# ATMEGA16_S52.net
KiCad netlist of a schematic drawn in Altium Designer
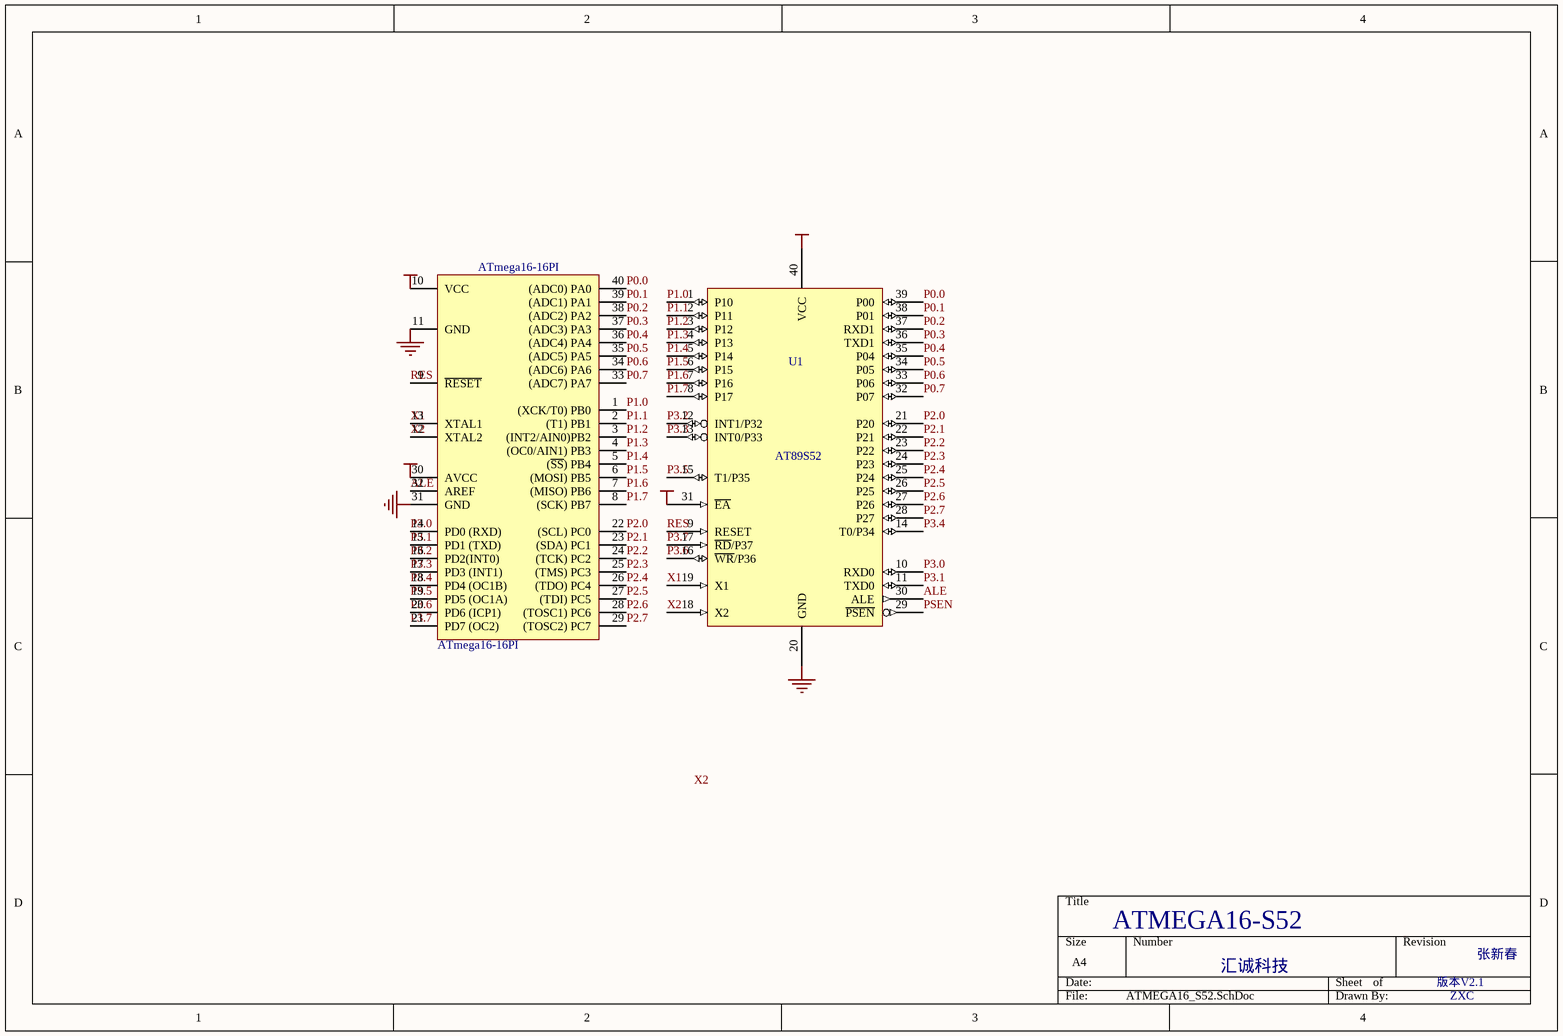
[diagram p0: ATMEGA16_S52.SchDoc]

(export (version "E")
  (design (tool "Eeschema 10.0.6"))
  (components
    (comp (ref "ATmega16-16PI")
      (value "ATmega16-16PI")
      (footprint "底座DIP-40/引脚15.24mm")
      (description "8 位微处理器/40引脚")
      (fields (field (name "发布者") "磊元工作室"))
      (libsource (lib "微控制处理器") (part "ATmega16-P"))
    )
    (comp (ref "U1") (value "AT89S52") (footprint "DIP-40") (libsource (lib "OldCow1 (2)") (part "8051")))
  )
  (nets
    (net (code "1") (name "/ALE") (class "Default")
      (node (ref "ATmega16-16PI") (pin "32") (pinfunction "AREF_32") (pintype "passive"))
      (node (ref "U1") (pin "30") (pinfunction "ALE_30") (pintype "output"))
    )
    (net (code "2") (name "/P0.0") (class "Default")
      (node (ref "ATmega16-16PI") (pin "40") (pinfunction "(ADC0)_PA0_40") (pintype "passive"))
      (node (ref "U1") (pin "39") (pinfunction "P00_39") (pintype "bidirectional"))
    )
    (net (code "3") (name "/P0.1") (class "Default")
      (node (ref "ATmega16-16PI") (pin "39") (pinfunction "(ADC1)_PA1_39") (pintype "passive"))
      (node (ref "U1") (pin "38") (pinfunction "P01_38") (pintype "bidirectional"))
    )
    (net (code "4") (name "/P0.2") (class "Default")
      (node (ref "ATmega16-16PI") (pin "38") (pinfunction "(ADC2)_PA2_38") (pintype "passive"))
      (node (ref "U1") (pin "37") (pinfunction "RXD1_37") (pintype "bidirectional"))
    )
    (net (code "5") (name "/P0.3") (class "Default")
      (node (ref "ATmega16-16PI") (pin "37") (pinfunction "(ADC3)_PA3_37") (pintype "passive"))
      (node (ref "U1") (pin "36") (pinfunction "TXD1_36") (pintype "bidirectional"))
    )
    (net (code "6") (name "/P0.4") (class "Default")
      (node (ref "ATmega16-16PI") (pin "36") (pinfunction "(ADC4)_PA4_36") (pintype "passive"))
      (node (ref "U1") (pin "35") (pinfunction "P04_35") (pintype "bidirectional"))
    )
    (net (code "7") (name "/P0.5") (class "Default")
      (node (ref "ATmega16-16PI") (pin "35") (pinfunction "(ADC5)_PA5_35") (pintype "passive"))
      (node (ref "U1") (pin "34") (pinfunction "P05_34") (pintype "bidirectional"))
    )
    (net (code "8") (name "/P0.6") (class "Default")
      (node (ref "ATmega16-16PI") (pin "34") (pinfunction "(ADC6)_PA6_34") (pintype "passive"))
      (node (ref "U1") (pin "33") (pinfunction "P06_33") (pintype "bidirectional"))
    )
    (net (code "9") (name "/P0.7") (class "Default")
      (node (ref "ATmega16-16PI") (pin "33") (pinfunction "(ADC7)_PA7_33") (pintype "passive"))
      (node (ref "U1") (pin "32") (pinfunction "P07_32") (pintype "bidirectional"))
    )
    (net (code "10") (name "/P1.0") (class "Default")
      (node (ref "ATmega16-16PI") (pin "1") (pinfunction "(XCK/T0)_PB0_1") (pintype "passive"))
      (node (ref "U1") (pin "1") (pinfunction "P10_1") (pintype "bidirectional"))
    )
    (net (code "11") (name "/P1.1") (class "Default")
      (node (ref "ATmega16-16PI") (pin "2") (pinfunction "(T1)_PB1_2") (pintype "passive"))
      (node (ref "U1") (pin "2") (pinfunction "P11_2") (pintype "bidirectional"))
    )
    (net (code "12") (name "/P1.2") (class "Default")
      (node (ref "ATmega16-16PI") (pin "3") (pinfunction "(INT2/AIN0)PB2_3") (pintype "passive"))
      (node (ref "U1") (pin "3") (pinfunction "P12_3") (pintype "bidirectional"))
    )
    (net (code "13") (name "/P1.3") (class "Default")
      (node (ref "ATmega16-16PI") (pin "4") (pinfunction "(OC0/AIN1)_PB3_4") (pintype "passive"))
      (node (ref "U1") (pin "4") (pinfunction "P13_4") (pintype "bidirectional"))
    )
    (net (code "14") (name "/P1.4") (class "Default")
      (node (ref "ATmega16-16PI") (pin "5") (pinfunction "(~{SS})_PB4_5") (pintype "passive"))
      (node (ref "U1") (pin "5") (pinfunction "P14_5") (pintype "bidirectional"))
    )
    (net (code "15") (name "/P1.5") (class "Default")
      (node (ref "ATmega16-16PI") (pin "6") (pinfunction "(MOSI)_PB5_6") (pintype "passive"))
      (node (ref "U1") (pin "6") (pinfunction "P15_6") (pintype "bidirectional"))
    )
    (net (code "16") (name "/P1.6") (class "Default")
      (node (ref "ATmega16-16PI") (pin "7") (pinfunction "(MISO)_PB6_7") (pintype "passive"))
      (node (ref "U1") (pin "7") (pinfunction "P16_7") (pintype "bidirectional"))
    )
    (net (code "17") (name "/P1.7") (class "Default")
      (node (ref "ATmega16-16PI") (pin "8") (pinfunction "(SCK)_PB7_8") (pintype "passive"))
      (node (ref "U1") (pin "8") (pinfunction "P17_8") (pintype "bidirectional"))
    )
    (net (code "18") (name "/P2.0") (class "Default")
      (node (ref "ATmega16-16PI") (pin "22") (pinfunction "(SCL)_PC0_22") (pintype "passive"))
      (node (ref "U1") (pin "21") (pinfunction "P20_21") (pintype "bidirectional"))
    )
    (net (code "19") (name "/P2.1") (class "Default")
      (node (ref "ATmega16-16PI") (pin "23") (pinfunction "(SDA)_PC1_23") (pintype "passive"))
      (node (ref "U1") (pin "22") (pinfunction "P21_22") (pintype "bidirectional"))
    )
    (net (code "20") (name "/P2.2") (class "Default")
      (node (ref "ATmega16-16PI") (pin "24") (pinfunction "(TCK)_PC2_24") (pintype "passive"))
      (node (ref "U1") (pin "23") (pinfunction "P22_23") (pintype "bidirectional"))
    )
    (net (code "21") (name "/P2.3") (class "Default")
      (node (ref "ATmega16-16PI") (pin "25") (pinfunction "(TMS)_PC3_25") (pintype "passive"))
      (node (ref "U1") (pin "24") (pinfunction "P23_24") (pintype "bidirectional"))
    )
    (net (code "22") (name "/P2.4") (class "Default")
      (node (ref "ATmega16-16PI") (pin "26") (pinfunction "(TDO)_PC4_26") (pintype "passive"))
      (node (ref "U1") (pin "25") (pinfunction "P24_25") (pintype "bidirectional"))
    )
    (net (code "23") (name "/P2.5") (class "Default")
      (node (ref "ATmega16-16PI") (pin "27") (pinfunction "(TDI)_PC5_27") (pintype "passive"))
      (node (ref "U1") (pin "26") (pinfunction "P25_26") (pintype "bidirectional"))
    )
    (net (code "24") (name "/P2.6") (class "Default")
      (node (ref "ATmega16-16PI") (pin "28") (pinfunction "(TOSC1)_PC6_28") (pintype "passive"))
      (node (ref "U1") (pin "27") (pinfunction "P26_27") (pintype "bidirectional"))
    )
    (net (code "25") (name "/P2.7") (class "Default")
      (node (ref "ATmega16-16PI") (pin "29") (pinfunction "(TOSC2)_PC7_29") (pintype "passive"))
      (node (ref "U1") (pin "28") (pinfunction "P27_28") (pintype "bidirectional"))
    )
    (net (code "26") (name "/P3.0") (class "Default")
      (node (ref "ATmega16-16PI") (pin "14") (pinfunction "PD0_(RXD)_14") (pintype "passive"))
      (node (ref "U1") (pin "10") (pinfunction "RXD0_10") (pintype "bidirectional"))
    )
    (net (code "27") (name "/P3.1") (class "Default")
      (node (ref "ATmega16-16PI") (pin "15") (pinfunction "PD1_(TXD)_15") (pintype "passive"))
      (node (ref "U1") (pin "11") (pinfunction "TXD0_11") (pintype "bidirectional"))
    )
    (net (code "28") (name "/P3.2") (class "Default")
      (node (ref "ATmega16-16PI") (pin "16") (pinfunction "PD2(INT0)_16") (pintype "passive"))
      (node (ref "U1") (pin "12") (pinfunction "INT1/P32_12") (pintype "bidirectional"))
    )
    (net (code "29") (name "/P3.3") (class "Default")
      (node (ref "ATmega16-16PI") (pin "17") (pinfunction "PD3_(INT1)_17") (pintype "passive"))
      (node (ref "U1") (pin "13") (pinfunction "INT0/P33_13") (pintype "bidirectional"))
    )
    (net (code "30") (name "/P3.4") (class "Default")
      (node (ref "ATmega16-16PI") (pin "18") (pinfunction "PD4_(OC1B)_18") (pintype "passive"))
      (node (ref "U1") (pin "14") (pinfunction "T0/P34_14") (pintype "bidirectional"))
    )
    (net (code "31") (name "/P3.5") (class "Default")
      (node (ref "ATmega16-16PI") (pin "19") (pinfunction "PD5_(OC1A)_19") (pintype "passive"))
      (node (ref "U1") (pin "15") (pinfunction "T1/P35_15") (pintype "bidirectional"))
    )
    (net (code "32") (name "/P3.6") (class "Default")
      (node (ref "ATmega16-16PI") (pin "20") (pinfunction "PD6_(ICP1)_20") (pintype "passive"))
      (node (ref "U1") (pin "16") (pinfunction "~{WR}/P36_16") (pintype "bidirectional"))
    )
    (net (code "33") (name "/P3.7") (class "Default")
      (node (ref "ATmega16-16PI") (pin "21") (pinfunction "PD7_(OC2)_21") (pintype "passive"))
      (node (ref "U1") (pin "17") (pinfunction "~{RD}/P37_17") (pintype "input"))
    )
    (net (code "34") (name "/PSEN") (class "Default")
      (node (ref "U1") (pin "29") (pinfunction "~{PSEN}_29") (pintype "output"))
    )
    (net (code "35") (name "/RES") (class "Default")
      (node (ref "ATmega16-16PI") (pin "9") (pinfunction "~{RESET}_9") (pintype "passive"))
      (node (ref "U1") (pin "9") (pinfunction "RESET_9") (pintype "input"))
    )
    (net (code "36") (name "/X1") (class "Default")
      (node (ref "ATmega16-16PI") (pin "13") (pinfunction "XTAL1_13") (pintype "passive"))
      (node (ref "U1") (pin "19") (pinfunction "X1_19") (pintype "input"))
    )
    (net (code "37") (name "/X2") (class "Default")
      (node (ref "ATmega16-16PI") (pin "12") (pinfunction "XTAL2_12") (pintype "passive"))
      (node (ref "U1") (pin "18") (pinfunction "X2_18") (pintype "input"))
    )
    (net (code "38") (name "GND") (class "Default")
      (node (ref "ATmega16-16PI") (pin "11") (pinfunction "GND_11") (pintype "passive"))
      (node (ref "ATmega16-16PI") (pin "31") (pinfunction "GND_31") (pintype "passive"))
      (node (ref "U1") (pin "20") (pinfunction "GND_20") (pintype "power_in"))
    )
    (net (code "39") (name "VCC") (class "Default")
      (node (ref "ATmega16-16PI") (pin "10") (pinfunction "VCC_10") (pintype "passive"))
      (node (ref "ATmega16-16PI") (pin "30") (pinfunction "AVCC_30") (pintype "passive"))
      (node (ref "U1") (pin "31") (pinfunction "~{EA}_31") (pintype "input"))
      (node (ref "U1") (pin "40") (pinfunction "VCC_40") (pintype "power_in"))
    )
  )
)
